# rx_ok.net
KiCad netlist of a schematic drawn in EAGLE
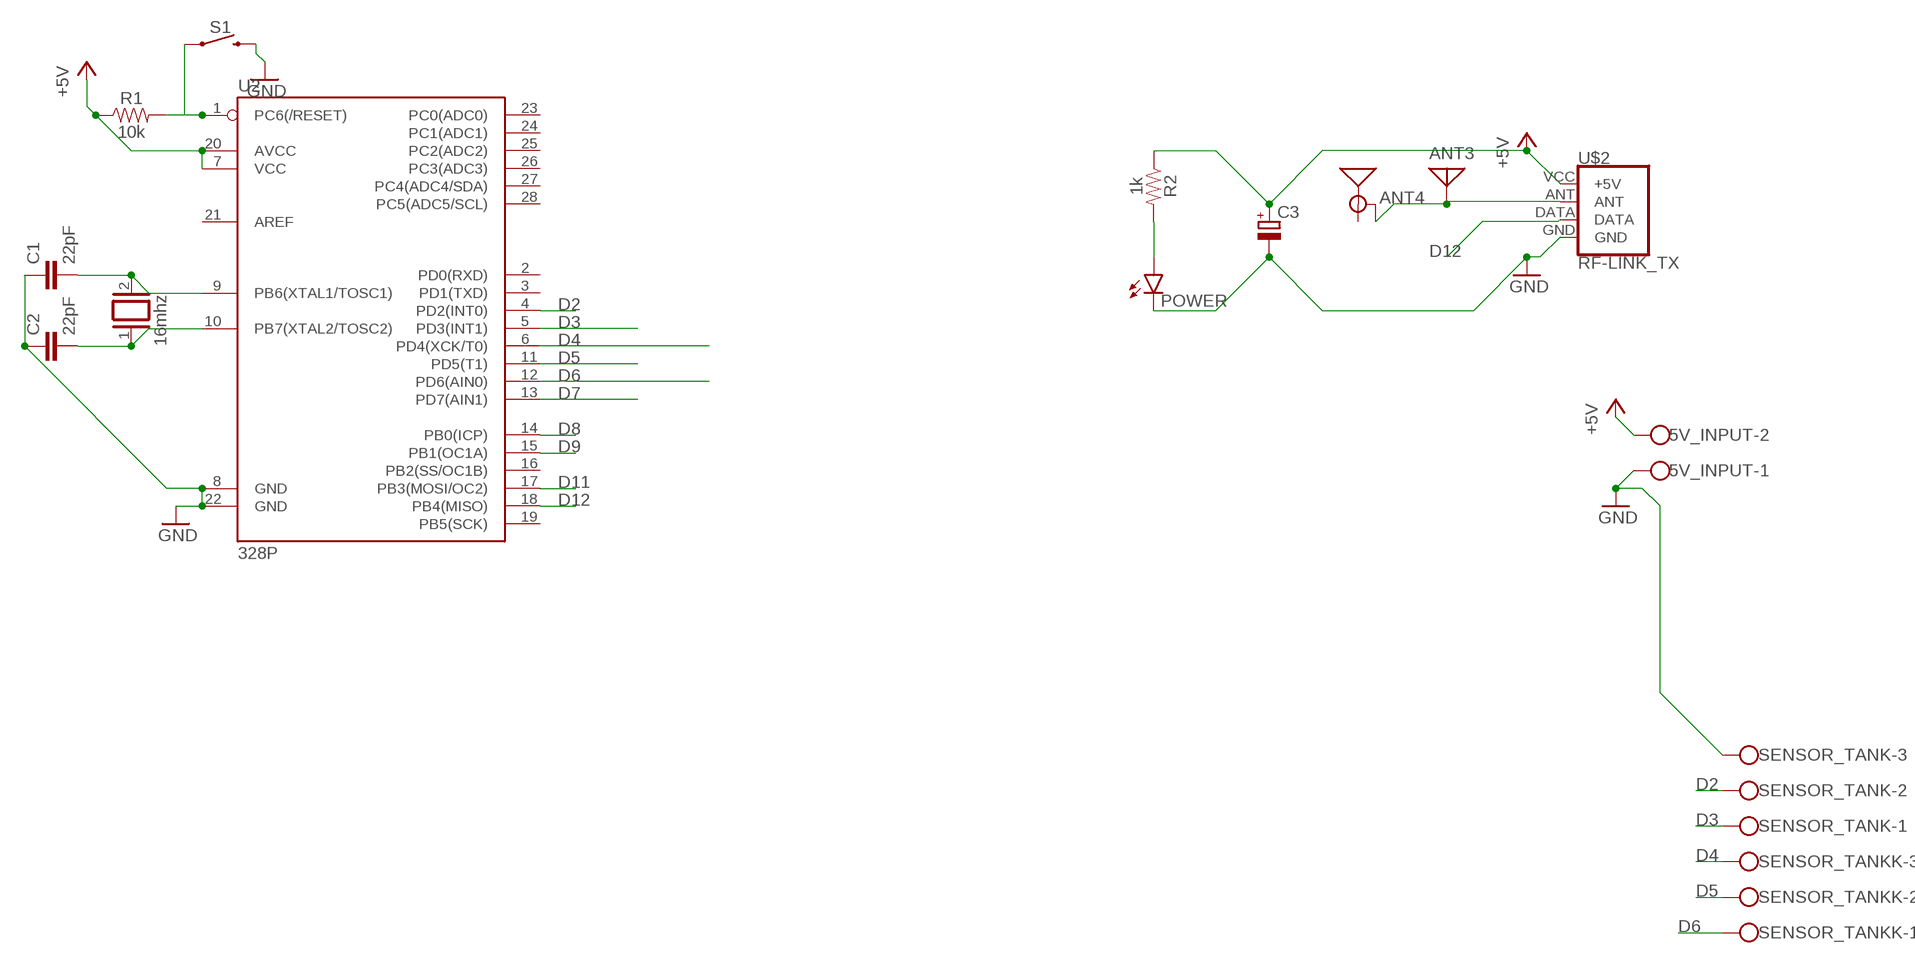
[diagram p0: schematic, sheet 1]

(export (version "E")
  (design (tool "Eeschema 10.0.6"))
  (components
    (comp (ref "5V_INPUT")
      (value "W237-102")
      (footprint "eagle-import:W237-102")
      (fields (field (name "MPN") "237-102"))
      (libsource (lib "eagle-import") (part "W237-102"))
    )
    (comp (ref "ANT3")
      (value "ANTENNA")
      (footprint "eagle-import:PAD-01")
      (libsource (lib "eagle-import") (part "ANTENNA"))
    )
    (comp (ref "ANT4")
      (value "ANTENNA-GROUNDEDTRACE-15.2MM")
      (footprint "eagle-import:TRACE_ANTENNA_2.4GHZ_15.2MM")
      (libsource (lib "eagle-import") (part "ANTENNA-GROUNDEDTRACE-15.2MM"))
    )
    (comp (ref "C1")
      (value "22pF")
      (footprint "eagle-import:CAP-PTH-2.54")
      (libsource (lib "eagle-import") (part "22PF-PTH-2.54MM-200V-5%"))
    )
    (comp (ref "C2")
      (value "22pF")
      (footprint "eagle-import:CAP-PTH-2.54")
      (libsource (lib "eagle-import") (part "22PF-PTH-2.54MM-200V-5%"))
    )
    (comp (ref "C3")
      (value "C-POL_RADIAL-20MM-DIA")
      (footprint "eagle-import:CAPPRD550W60D1200H2000B")
      (libsource (lib "eagle-import") (part "C-POLRADIAL-20MM-DIA_"))
    )
    (comp (ref "POWER")
      (value "LED3MM")
      (footprint "eagle-import:LED3MM")
      (libsource (lib "eagle-import") (part "LED3MM"))
    )
    (comp (ref "Q1")
      (value "16mhz")
      (footprint "eagle-import:QS")
      (libsource (lib "eagle-import") (part "XTAL/S"))
    )
    (comp (ref "R1")
      (value "10k")
      (footprint "eagle-import:AXIAL-0.3")
      (libsource (lib "eagle-import") (part "1KOHM-HORIZ-1/4W-5%"))
    )
    (comp (ref "R2")
      (value "1k")
      (footprint "eagle-import:AXIAL-0.3")
      (libsource (lib "eagle-import") (part "1KOHM-HORIZ-1/4W-1%"))
    )
    (comp (ref "S1")
      (value "MOMENTARY-SWITCH-SPST-PTH-6.0MM")
      (footprint "eagle-import:TACTILE_SWITCH_PTH_6.0MM")
      (libsource (lib "eagle-import") (part "MOMENTARY-SWITCH-SPST-PTH-6.0MM"))
    )
    (comp (ref "SENSOR_TANK")
      (value "W237-103")
      (footprint "eagle-import:W237-103")
      (fields (field (name "MPN") "237-103"))
      (libsource (lib "eagle-import") (part "W237-103"))
    )
    (comp (ref "SENSOR_TANKK")
      (value "W237-103")
      (footprint "eagle-import:W237-103")
      (fields (field (name "MPN") "237-103"))
      (libsource (lib "eagle-import") (part "W237-103"))
    )
    (comp (ref "U$2")
      (value "RF-LINK_TX")
      (footprint "eagle-import:RF-LINK_TX")
      (libsource (lib "eagle-import") (part "RF-LINK_TX"))
    )
    (comp (ref "U2")
      (value "328P")
      (footprint "eagle-import:DIP28")
      (libsource (lib "eagle-import") (part "ATMEGA328P_PDIP"))
    )
  )
  (nets
    (net (code "1") (name "+5V") (class "Default")
      (node (ref "5V_INPUT") (pin "2") (pinfunction "KL_2") (pintype "passive"))
      (node (ref "C3") (pin "1") (pinfunction "+_1") (pintype "passive"))
      (node (ref "R1") (pin "P$1") (pinfunction "1_P$1") (pintype "passive"))
      (node (ref "R2") (pin "P$1") (pinfunction "1_P$1") (pintype "passive"))
      (node (ref "U$2") (pin "VCC") (pinfunction "+5V_VCC") (pintype "power_in"))
      (node (ref "U2") (pin "20") (pinfunction "AVCC_20") (pintype "bidirectional"))
      (node (ref "U2") (pin "7") (pinfunction "VCC_7") (pintype "bidirectional"))
    )
    (net (code "2") (name "/D2") (class "Default")
      (node (ref "SENSOR_TANK") (pin "2") (pinfunction "KL_2") (pintype "passive"))
      (node (ref "U2") (pin "4") (pinfunction "PD2(INT0)_4") (pintype "bidirectional"))
    )
    (net (code "3") (name "/D3") (class "Default")
      (node (ref "SENSOR_TANK") (pin "1") (pinfunction "KL_1") (pintype "passive"))
      (node (ref "U2") (pin "5") (pinfunction "PD3(INT1)_5") (pintype "bidirectional"))
    )
    (net (code "4") (name "/D4") (class "Default")
      (node (ref "SENSOR_TANKK") (pin "3") (pinfunction "KL_3") (pintype "passive"))
      (node (ref "U2") (pin "6") (pinfunction "PD4(XCK/T0)_6") (pintype "bidirectional"))
    )
    (net (code "5") (name "/D5") (class "Default")
      (node (ref "SENSOR_TANKK") (pin "2") (pinfunction "KL_2") (pintype "passive"))
      (node (ref "U2") (pin "11") (pinfunction "PD5(T1)_11") (pintype "bidirectional"))
    )
    (net (code "6") (name "/D6") (class "Default")
      (node (ref "SENSOR_TANKK") (pin "1") (pinfunction "KL_1") (pintype "passive"))
      (node (ref "U2") (pin "12") (pinfunction "PD6(AIN0)_12") (pintype "bidirectional"))
    )
    (net (code "7") (name "/D7") (class "Default")
      (node (ref "U2") (pin "13") (pinfunction "PD7(AIN1)_13") (pintype "bidirectional"))
    )
    (net (code "8") (name "/D8") (class "Default")
      (node (ref "U2") (pin "14") (pinfunction "PB0(ICP)_14") (pintype "bidirectional"))
    )
    (net (code "9") (name "/D9") (class "Default")
      (node (ref "U2") (pin "15") (pinfunction "PB1(OC1A)_15") (pintype "bidirectional"))
    )
    (net (code "10") (name "/D11") (class "Default")
      (node (ref "U2") (pin "17") (pinfunction "PB3(MOSI/OC2)_17") (pintype "bidirectional"))
    )
    (net (code "11") (name "/D12") (class "Default")
      (node (ref "U$2") (pin "DATA") (pinfunction "DATA_DATA") (pintype "input"))
      (node (ref "U2") (pin "18") (pinfunction "PB4(MISO)_18") (pintype "bidirectional"))
    )
    (net (code "12") (name "GND") (class "Default")
      (node (ref "5V_INPUT") (pin "1") (pinfunction "KL_1") (pintype "passive"))
      (node (ref "C1") (pin "1") (pinfunction "1_1") (pintype "passive"))
      (node (ref "C2") (pin "1") (pinfunction "1_1") (pintype "passive"))
      (node (ref "C3") (pin "2") (pinfunction "-_2") (pintype "passive"))
      (node (ref "POWER") (pin "K") (pinfunction "C_K") (pintype "passive"))
      (node (ref "S1") (pin "3") (pinfunction "2_3") (pintype "passive"))
      (node (ref "SENSOR_TANK") (pin "3") (pinfunction "KL_3") (pintype "passive"))
      (node (ref "U$2") (pin "GND") (pinfunction "GND_GND") (pintype "power_in"))
      (node (ref "U2") (pin "22") (pinfunction "GND_22") (pintype "bidirectional"))
      (node (ref "U2") (pin "8") (pinfunction "GND_8") (pintype "bidirectional"))
    )
    (net (code "13") (name "Net-(ANT3-Pad1)") (class "Default")
      (node (ref "ANT3") (pin "1") (pinfunction "1_1") (pintype "output"))
      (node (ref "ANT4") (pin "GND") (pinfunction "GND_GND") (pintype "bidirectional"))
      (node (ref "U$2") (pin "ANT") (pinfunction "ANT_ANT") (pintype "passive"))
    )
    (net (code "14") (name "Net-(R1-2)") (class "Default")
      (node (ref "R1") (pin "P$2") (pinfunction "2_P$2") (pintype "passive"))
      (node (ref "S1") (pin "1") (pinfunction "1_1") (pintype "passive"))
      (node (ref "U2") (pin "1") (pinfunction "PC6(/RESET)_1") (pintype "bidirectional"))
    )
    (net (code "15") (name "Net-(R2-2)") (class "Default")
      (node (ref "POWER") (pin "A") (pinfunction "A_A") (pintype "passive"))
      (node (ref "R2") (pin "P$2") (pinfunction "2_P$2") (pintype "passive"))
    )
    (net (code "16") (name "Net-(U2-PB6(XTAL1{slash}TOSC1))") (class "Default")
      (node (ref "C1") (pin "2") (pinfunction "2_2") (pintype "passive"))
      (node (ref "Q1") (pin "2") (pinfunction "2_2") (pintype "passive"))
      (node (ref "U2") (pin "9") (pinfunction "PB6(XTAL1/TOSC1)_9") (pintype "bidirectional"))
    )
    (net (code "17") (name "Net-(U2-PB7(XTAL2{slash}TOSC2))") (class "Default")
      (node (ref "C2") (pin "2") (pinfunction "2_2") (pintype "passive"))
      (node (ref "Q1") (pin "1") (pinfunction "1_1") (pintype "passive"))
      (node (ref "U2") (pin "10") (pinfunction "PB7(XTAL2/TOSC2)_10") (pintype "bidirectional"))
    )
    (net (code "18") (name "unconnected-(ANT4-SIGNAL-PadANT)") (class "Default")
      (node (ref "ANT4") (pin "ANT") (pinfunction "SIGNAL_ANT") (pintype "bidirectional"))
    )
    (net (code "19") (name "unconnected-(U2-AREF-Pad21)") (class "Default")
      (node (ref "U2") (pin "21") (pinfunction "AREF_21") (pintype "bidirectional"))
    )
    (net (code "20") (name "unconnected-(U2-PB2(SS{slash}OC1B)-Pad16)") (class "Default")
      (node (ref "U2") (pin "16") (pinfunction "PB2(SS/OC1B)_16") (pintype "bidirectional"))
    )
    (net (code "21") (name "unconnected-(U2-PB5(SCK)-Pad19)") (class "Default")
      (node (ref "U2") (pin "19") (pinfunction "PB5(SCK)_19") (pintype "bidirectional"))
    )
    (net (code "22") (name "unconnected-(U2-PC0(ADC0)-Pad23)") (class "Default")
      (node (ref "U2") (pin "23") (pinfunction "PC0(ADC0)_23") (pintype "bidirectional"))
    )
    (net (code "23") (name "unconnected-(U2-PC1(ADC1)-Pad24)") (class "Default")
      (node (ref "U2") (pin "24") (pinfunction "PC1(ADC1)_24") (pintype "bidirectional"))
    )
    (net (code "24") (name "unconnected-(U2-PC2(ADC2)-Pad25)") (class "Default")
      (node (ref "U2") (pin "25") (pinfunction "PC2(ADC2)_25") (pintype "bidirectional"))
    )
    (net (code "25") (name "unconnected-(U2-PC3(ADC3)-Pad26)") (class "Default")
      (node (ref "U2") (pin "26") (pinfunction "PC3(ADC3)_26") (pintype "bidirectional"))
    )
    (net (code "26") (name "unconnected-(U2-PC4(ADC4{slash}SDA)-Pad27)") (class "Default")
      (node (ref "U2") (pin "27") (pinfunction "PC4(ADC4/SDA)_27") (pintype "bidirectional"))
    )
    (net (code "27") (name "unconnected-(U2-PC5(ADC5{slash}SCL)-Pad28)") (class "Default")
      (node (ref "U2") (pin "28") (pinfunction "PC5(ADC5/SCL)_28") (pintype "bidirectional"))
    )
    (net (code "28") (name "unconnected-(U2-PD0(RXD)-Pad2)") (class "Default")
      (node (ref "U2") (pin "2") (pinfunction "PD0(RXD)_2") (pintype "bidirectional"))
    )
    (net (code "29") (name "unconnected-(U2-PD1(TXD)-Pad3)") (class "Default")
      (node (ref "U2") (pin "3") (pinfunction "PD1(TXD)_3") (pintype "bidirectional"))
    )
  )
)
